# serial_com.net
KiCad netlist of a schematic drawn in Altium Designer
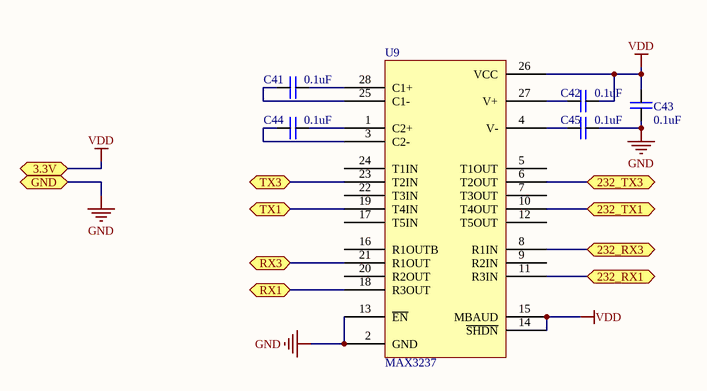
[diagram p0: serial_com.SchDoc]

(export (version "E")
  (design (tool "Eeschema 10.0.6"))
  (components
    (comp (ref "C41")
      (value "0.1uF")
      (footprint "CAP-0805")
      (fields (field (name "Comment") "CAP"))
      (libsource (lib "Schlib1") (part "CAP"))
    )
    (comp (ref "C42")
      (value "0.1uF")
      (footprint "CAP-0805")
      (fields (field (name "Comment") "CAP"))
      (libsource (lib "Schlib1") (part "CAP"))
    )
    (comp (ref "C43")
      (value "0.1uF")
      (footprint "CAP-0805")
      (fields (field (name "Comment") "CAP"))
      (libsource (lib "Schlib1") (part "CAP"))
    )
    (comp (ref "C44")
      (value "0.1uF")
      (footprint "CAP-0805")
      (fields (field (name "Comment") "CAP"))
      (libsource (lib "Schlib1") (part "CAP"))
    )
    (comp (ref "C45")
      (value "0.1uF")
      (footprint "CAP-0805")
      (fields (field (name "Comment") "CAP"))
      (libsource (lib "Schlib1") (part "CAP"))
    )
    (comp (ref "U9") (value "MAX3237") (footprint "SSOP28") (libsource (lib "Schlib1") (part "MAX3237")))
  )
  (nets
    (net (code "1") (name "/232_RX1") (class "Default")
      (node (ref "U9") (pin "11") (pinfunction "R3IN_11") (pintype "passive"))
    )
    (net (code "2") (name "/232_RX3") (class "Default")
      (node (ref "U9") (pin "8") (pinfunction "R1IN_8") (pintype "passive"))
    )
    (net (code "3") (name "/232_TX1") (class "Default")
      (node (ref "U9") (pin "10") (pinfunction "T4OUT_10") (pintype "passive"))
    )
    (net (code "4") (name "/232_TX3") (class "Default")
      (node (ref "U9") (pin "6") (pinfunction "T2OUT_6") (pintype "passive"))
    )
    (net (code "5") (name "/RX1") (class "Default")
      (node (ref "U9") (pin "18") (pinfunction "R3OUT_18") (pintype "passive"))
    )
    (net (code "6") (name "/RX3") (class "Default")
      (node (ref "U9") (pin "21") (pinfunction "R1OUT_21") (pintype "passive"))
    )
    (net (code "7") (name "/TX1") (class "Default")
      (node (ref "U9") (pin "19") (pinfunction "T4IN_19") (pintype "passive"))
    )
    (net (code "8") (name "/TX3") (class "Default")
      (node (ref "U9") (pin "23") (pinfunction "T2IN_23") (pintype "passive"))
    )
    (net (code "9") (name "GND") (class "Default")
      (node (ref "C43") (pin "1") (pintype "passive"))
      (node (ref "C45") (pin "2") (pintype "passive"))
      (node (ref "U9") (pin "13") (pinfunction "~{EN}_13") (pintype "passive"))
      (node (ref "U9") (pin "2") (pinfunction "GND_2") (pintype "passive"))
    )
    (net (code "10") (name "Net-(U9-C1+)") (class "Default")
      (node (ref "C41") (pin "2") (pintype "passive"))
      (node (ref "U9") (pin "28") (pinfunction "C1+_28") (pintype "passive"))
    )
    (net (code "11") (name "Net-(U9-C1-)") (class "Default")
      (node (ref "C41") (pin "1") (pintype "passive"))
      (node (ref "U9") (pin "25") (pinfunction "C1-_25") (pintype "passive"))
    )
    (net (code "12") (name "Net-(U9-C2+)") (class "Default")
      (node (ref "C44") (pin "2") (pintype "passive"))
      (node (ref "U9") (pin "1") (pinfunction "C2+_1") (pintype "passive"))
    )
    (net (code "13") (name "Net-(U9-C2-)") (class "Default")
      (node (ref "C44") (pin "1") (pintype "passive"))
      (node (ref "U9") (pin "3") (pinfunction "C2-_3") (pintype "passive"))
    )
    (net (code "14") (name "Net-(U9-V+)") (class "Default")
      (node (ref "C42") (pin "1") (pintype "passive"))
      (node (ref "U9") (pin "27") (pinfunction "V+_27") (pintype "passive"))
    )
    (net (code "15") (name "Net-(U9-V-)") (class "Default")
      (node (ref "C45") (pin "1") (pintype "passive"))
      (node (ref "U9") (pin "4") (pinfunction "V-_4") (pintype "passive"))
    )
    (net (code "16") (name "VDD") (class "Default")
      (node (ref "C42") (pin "2") (pintype "passive"))
      (node (ref "C43") (pin "2") (pintype "passive"))
      (node (ref "U9") (pin "14") (pinfunction "~{SHDN}_14") (pintype "passive"))
      (node (ref "U9") (pin "15") (pinfunction "MBAUD_15") (pintype "passive"))
      (node (ref "U9") (pin "26") (pinfunction "VCC_26") (pintype "passive"))
    )
    (net (code "17") (name "unconnected-(U9-R1OUTB-Pad16)") (class "Default")
      (node (ref "U9") (pin "16") (pinfunction "R1OUTB_16") (pintype "passive"))
    )
    (net (code "18") (name "unconnected-(U9-R2IN-Pad9)") (class "Default")
      (node (ref "U9") (pin "9") (pinfunction "R2IN_9") (pintype "passive"))
    )
    (net (code "19") (name "unconnected-(U9-R2OUT-Pad20)") (class "Default")
      (node (ref "U9") (pin "20") (pinfunction "R2OUT_20") (pintype "passive"))
    )
    (net (code "20") (name "unconnected-(U9-T1IN-Pad24)") (class "Default")
      (node (ref "U9") (pin "24") (pinfunction "T1IN_24") (pintype "passive"))
    )
    (net (code "21") (name "unconnected-(U9-T1OUT-Pad5)") (class "Default")
      (node (ref "U9") (pin "5") (pinfunction "T1OUT_5") (pintype "passive"))
    )
    (net (code "22") (name "unconnected-(U9-T3IN-Pad22)") (class "Default")
      (node (ref "U9") (pin "22") (pinfunction "T3IN_22") (pintype "passive"))
    )
    (net (code "23") (name "unconnected-(U9-T3OUT-Pad7)") (class "Default")
      (node (ref "U9") (pin "7") (pinfunction "T3OUT_7") (pintype "passive"))
    )
    (net (code "24") (name "unconnected-(U9-T5IN-Pad17)") (class "Default")
      (node (ref "U9") (pin "17") (pinfunction "T5IN_17") (pintype "passive"))
    )
    (net (code "25") (name "unconnected-(U9-T5OUT-Pad12)") (class "Default")
      (node (ref "U9") (pin "12") (pinfunction "T5OUT_12") (pintype "passive"))
    )
  )
)
